# ELoad_Control_Assembly_Gen_2_-_PSU_-_Rev.net
KiCad netlist of a schematic drawn in Altium Designer
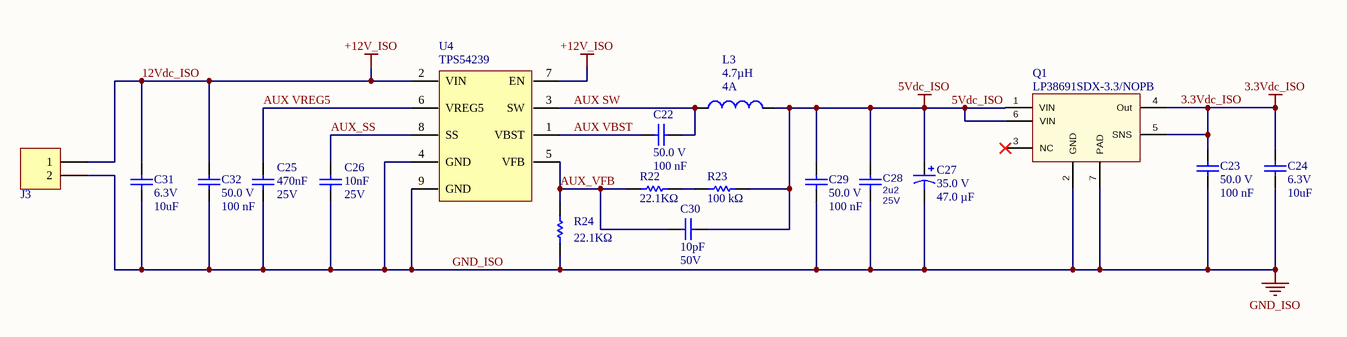
[diagram p0: ELoad Control Assembly Gen 2 - PSU - Rev 2.SchDoc]

(export (version "E")
  (design (tool "Eeschema 10.0.6"))
  (components
    (comp (ref "C22")
      (value "Cap")
      (footprint "Cap,0805")
      (description "Capacitor; Ceramic; Cap 0.1 uF; Tol 5%; Vol-Rtg 50 VDC; SMT; 0805; X7R; Tape & Reel")
      (fields
        (field (name "MANUFACTURER PART NUMBER") "08055C104JAT2A")
        (field (name "VOLTAGE RATING (DC)") "50.0 V")
        (field (name "CAPACITANCE") "100 nF")
      )
      (libsource (lib "Master SEPT2019") (part "Cap,0805,100nf,50V,5%,08055C104JAT2A"))
    )
    (comp (ref "C23")
      (value "Cap")
      (footprint "Cap,0805")
      (description "Capacitor; Ceramic; Cap 0.1 uF; Tol 5%; Vol-Rtg 50 VDC; SMT; 0805; X7R; Tape & Reel")
      (fields
        (field (name "MANUFACTURER PART NUMBER") "08055C104JAT2A")
        (field (name "VOLTAGE RATING (DC)") "50.0 V")
        (field (name "CAPACITANCE") "100 nF")
      )
      (libsource (lib "Master SEPT2019") (part "Cap,0805,100nf,50V,5%,08055C104JAT2A"))
    )
    (comp (ref "C24")
      (value "Cap")
      (footprint "Cap,0805")
      (description "CL21 Series 10 uF 6.3V ±10 % Tolerance X5R SMT Multilayer Ceramic Capacitor")
      (fields
        (field (name "TOLERANCE") "±10%")
        (field (name "VOLTAGE - RATED") "6.3V")
        (field (name "CAPACITANCE") "10uF")
      )
      (libsource (lib "Master SEPT2019") (part "Cap,0805,10uf,6.3V,10%,CL21A106KQFNNNG"))
    )
    (comp (ref "C25")
      (value "Cap")
      (footprint "Cap,0805")
      (description "0.47µF ±10% 25V Ceramic Capacitor X7R 0805 (2012 Metric)")
      (fields
        (field (name "MANUFACTURER") "TDK Corporation")
        (field (name "VOLTAGE RATING (DC)") "25V")
        (field (name "CAPACITANCE") "470nF")
      )
      (libsource (lib "Master SEPT2019") (part "Cap,0805,470nf,25V,10%,CGA4J2X7R1E474K125AA"))
    )
    (comp (ref "C26")
      (value "Cap")
      (footprint "Cap,0805")
      (description "CAP CER 10000PF 25V X7R 0805")
      (fields
        (field (name "MANUFACTURER") "Samsung Electro-Mechanics")
        (field (name "VOLTAGE RATING (DC)") "25V")
        (field (name "CAPACITANCE") "10nF")
      )
      (libsource (lib "Master SEPT2019") (part "Cap,0805,10nF,±10%,25Vdc"))
    )
    (comp (ref "C27")
      (value "Nichicon UCW1V470MCL1GS")
      (footprint "Cap, SMD, polerized, 5mm spacing")
      (description "47uF 35 V dc Aluminium Electrolytic Capacitor, CW Series 7000h 6.3(Dia.)x8.7mm")
      (fields
        (field (name "MANUFACTURER PART NUMBER") "UCW1V470MCL1GS")
        (field (name "VOLTAGE RATING (DC)") "35.0 V")
        (field (name "CAPACITANCE") "47.0 µF")
      )
      (libsource (lib "Master SEPT2019") (part "Cap, Polar,SMD, 47uF,35V,UCW1V470MCL1GS"))
    )
    (comp (ref "C28")
      (value "2u2")
      (footprint "res, 0805, HD")
      (description "Cap,SMD,MLCC,2.2uF 25V X7R 10%,0805")
      (fields (field (name "MANUFACTURER") "Murata") (field (name "VOLTAGE") "25V"))
      (libsource (lib "Master SEPT_2019") (part "Cap,0805,2.2uF,10%,25V"))
    )
    (comp (ref "C29")
      (value "Cap")
      (footprint "Cap,0805")
      (description "Capacitor; Ceramic; Cap 0.1 uF; Tol 5%; Vol-Rtg 50 VDC; SMT; 0805; X7R; Tape & Reel")
      (fields
        (field (name "MANUFACTURER PART NUMBER") "08055C104JAT2A")
        (field (name "VOLTAGE RATING (DC)") "50.0 V")
        (field (name "CAPACITANCE") "100 nF")
      )
      (libsource (lib "Master SEPT_2019") (part "Cap,0805,100nf,50V,5%,08055C104JAT2A"))
    )
    (comp (ref "C30")
      (value "CL21C100JBANNNC")
      (footprint "CAP, 0805, HD")
      (description "CAP CER 10PF 50V C0G/NP0 0805")
      (fields
        (field (name "MANUFACTURER") "Samsung Electro-Mechanics")
        (field (name "TOLERANCE") "±5%")
        (field (name "CAPACITANCE") "10pF")
        (field (name "VOLTAGE - RATED") "50V")
      )
      (libsource (lib "Master SEPT_2019") (part "Cap,0805,10pf,±5%,C0G, NP0,CL21C100JBANNNC"))
    )
    (comp (ref "C31")
      (value "Cap")
      (footprint "Cap,0805")
      (description "CL21 Series 10 uF 6.3V ±10 % Tolerance X5R SMT Multilayer Ceramic Capacitor")
      (fields
        (field (name "TOLERANCE") "±10%")
        (field (name "VOLTAGE - RATED") "6.3V")
        (field (name "CAPACITANCE") "10uF")
      )
      (libsource (lib "Master SEPT2019") (part "Cap,0805,10uf,6.3V,10%,CL21A106KQFNNNG"))
    )
    (comp (ref "C32")
      (value "Cap")
      (footprint "Cap,0805")
      (description "Capacitor; Ceramic; Cap 0.1 uF; Tol 5%; Vol-Rtg 50 VDC; SMT; 0805; X7R; Tape & Reel")
      (fields
        (field (name "MANUFACTURER PART NUMBER") "08055C104JAT2A")
        (field (name "VOLTAGE RATING (DC)") "50.0 V")
        (field (name "CAPACITANCE") "100 nF")
      )
      (libsource (lib "Master SEPT2019") (part "Cap,0805,100nf,50V,5%,08055C104JAT2A"))
    )
    (comp (ref "J3")
      (value "conn, through hole, molex, 2 pin, 0.1\",640456-2")
      (footprint "Conn, Molex, 2pin,0.1\" spacing")
      (description "Header, Friction Lock; MTA-100; 2; 250 VAC; Polyester; Tin; Copper Alloy; Tin")
      (libsource (lib "Master JULY2019") (part "conn, through hole, molex, 2 pin, 0.1{dblquote},640456-2"))
    )
    (comp (ref "L3")
      (value "1255AY-4R7M=P3")
      (footprint "Ind,Non-Stand,Murata,1255AY")
      (description "FIXED IND 4.7UH 4.5A 27.6 MOHM")
      (fields
        (field (name "MANUFACTURER") "Murata Electronics North America")
        (field (name "TOLERANCE") "±20%")
        (field (name "INDUCTANCE") "4.7µH")
        (field (name "CURRENT RATING (AMPS)") "4A")
      )
      (libsource (lib "Master SEPT_2019") (part "IND,NON-Stand,SMD,4.7uH,4.5A,27.6mOhm,1255AY-4R7M=P3"))
    )
    (comp (ref "Q1")
      (value "LP38691SDX-3.3/NOPB")
      (footprint "6-WSON (3x3)")
      (description "IC REG LIN POS ADJ 500MA 6WSON")
      (fields
        (field (name "MFG P/N") "LP38691SDX-3.3/NOPB")
        (field (name "MANUFACTURER") "Texas Instruments")
        (field (name "BASE PART NUMBER") "LP38691")
      )
      (libsource (lib "Master SEPT2019") (part "Reg,Linear,Fixed,500mA,10Vin_Max,3.3Vdc,LP38691SD-ADJ/NOPB"))
    )
    (comp (ref "R22")
      (value "RC0805FR-0722K1L")
      (footprint "res, 0805, HD")
      (description "22.1 kOhms ±1% 0.125W, 1/8W Chip Resistor 0805 (2012 Metric) Moisture Resistant Thick Film")
      (fields (field (name "RESISTANCE") "22.1KΩ"))
      (libsource (lib "Master SEPT_2019") (part "Res,0805,22.1K,1%,100ppm,RC0805FR-0722K1L"))
    )
    (comp (ref "R23")
      (value "Res,0805,100kΩ,1%,100ppm,CRCW0805100KFKEA")
      (footprint "res, 0805, HD")
      (description "100 kOhms ±1% 0.125W, 1/8W Chip Resistor 0805 (2012 Metric) Thick Film")
      (fields
        (field (name "MANUFACTURER PART NUMBER") "CRCW0805100KFKEA")
        (field (name "MANUFACTURER") "Vishay")
        (field (name "RESISTANCE") "100 kΩ")
      )
      (libsource (lib "Master SEPT2019") (part "Res,0805,100kΩ,1%,100ppm,CRCW0805100KFKEA"))
    )
    (comp (ref "R24")
      (value "RC0805FR-0722K1L")
      (footprint "res, 0805, HD")
      (description "22.1 kOhms ±1% 0.125W, 1/8W Chip Resistor 0805 (2012 Metric) Moisture Resistant Thick Film")
      (fields (field (name "RESISTANCE") "22.1KΩ"))
      (libsource (lib "Master SEPT_2019") (part "Res,0805,22.1K,1%,100ppm,RC0805FR-0722K1L"))
    )
    (comp (ref "U4")
      (value "TPS54239")
      (footprint "SOIC-8 PowerPad(pin4)")
      (libsource (lib "Master SEPT_2019") (part "Reg, Switching, Buck,23-4.5Vdcin,2A,TPS54239EDDAR"))
    )
  )
  (nets
    (net (code "1") (name "+12V_ISO") (class "Default")
      (node (ref "C31") (pin "2") (pinfunction "2_2") (pintype "passive"))
      (node (ref "C32") (pin "2") (pinfunction "2_2") (pintype "passive"))
      (node (ref "J3") (pin "1") (pinfunction "1_1") (pintype "passive"))
      (node (ref "U4") (pin "2") (pinfunction "VIN_2") (pintype "passive"))
      (node (ref "U4") (pin "7") (pinfunction "EN_7") (pintype "passive"))
    )
    (net (code "2") (name "/AUX SW") (class "Default")
      (node (ref "C22") (pin "1") (pinfunction "1_1") (pintype "passive"))
      (node (ref "L3") (pin "1") (pinfunction "1_1") (pintype "passive"))
      (node (ref "U4") (pin "3") (pinfunction "SW_3") (pintype "passive"))
    )
    (net (code "3") (name "/AUX VBST") (class "Default")
      (node (ref "C22") (pin "2") (pinfunction "2_2") (pintype "passive"))
      (node (ref "U4") (pin "1") (pinfunction "VBST_1") (pintype "passive"))
    )
    (net (code "4") (name "/AUX VREG5") (class "Default")
      (node (ref "C25") (pin "2") (pinfunction "2_2") (pintype "passive"))
      (node (ref "U4") (pin "6") (pinfunction "VREG5_6") (pintype "passive"))
    )
    (net (code "5") (name "/AUX_SS") (class "Default")
      (node (ref "C26") (pin "2") (pinfunction "2_2") (pintype "passive"))
      (node (ref "U4") (pin "8") (pinfunction "SS_8") (pintype "passive"))
    )
    (net (code "6") (name "/AUX_VFB") (class "Default")
      (node (ref "C30") (pin "2") (pinfunction "2_2") (pintype "passive"))
      (node (ref "R22") (pin "1") (pinfunction "1_1") (pintype "passive"))
      (node (ref "R24") (pin "2") (pinfunction "2_2") (pintype "passive"))
      (node (ref "U4") (pin "5") (pinfunction "VFB_5") (pintype "passive"))
    )
    (net (code "7") (name "3.3Vdc_ISO") (class "Default")
      (node (ref "C23") (pin "2") (pinfunction "2_2") (pintype "passive"))
      (node (ref "C24") (pin "2") (pinfunction "2_2") (pintype "passive"))
      (node (ref "Q1") (pin "4") (pinfunction "Out_4") (pintype "power_in"))
      (node (ref "Q1") (pin "5") (pinfunction "SNS_5") (pintype "passive"))
    )
    (net (code "8") (name "5Vdc_ISO") (class "Default")
      (node (ref "C27") (pin "1") (pinfunction "1_1") (pintype "passive"))
      (node (ref "C28") (pin "2") (pintype "passive"))
      (node (ref "C29") (pin "2") (pinfunction "2_2") (pintype "passive"))
      (node (ref "C30") (pin "1") (pinfunction "1_1") (pintype "passive"))
      (node (ref "L3") (pin "2") (pinfunction "2_2") (pintype "passive"))
      (node (ref "Q1") (pin "1") (pinfunction "VIN_1") (pintype "power_in"))
      (node (ref "Q1") (pin "6") (pinfunction "VIN_6") (pintype "power_in"))
      (node (ref "R23") (pin "1") (pinfunction "1_1") (pintype "passive"))
    )
    (net (code "9") (name "GND_ISO") (class "Default")
      (node (ref "C23") (pin "1") (pinfunction "1_1") (pintype "passive"))
      (node (ref "C24") (pin "1") (pinfunction "1_1") (pintype "passive"))
      (node (ref "C25") (pin "1") (pinfunction "1_1") (pintype "passive"))
      (node (ref "C26") (pin "1") (pinfunction "1_1") (pintype "passive"))
      (node (ref "C27") (pin "2") (pinfunction "2_2") (pintype "passive"))
      (node (ref "C28") (pin "1") (pintype "passive"))
      (node (ref "C29") (pin "1") (pinfunction "1_1") (pintype "passive"))
      (node (ref "C31") (pin "1") (pinfunction "1_1") (pintype "passive"))
      (node (ref "C32") (pin "1") (pinfunction "1_1") (pintype "passive"))
      (node (ref "J3") (pin "2") (pinfunction "2_2") (pintype "passive"))
      (node (ref "Q1") (pin "2") (pinfunction "GND_2") (pintype "power_in"))
      (node (ref "Q1") (pin "7") (pinfunction "PAD_7") (pintype "power_in"))
      (node (ref "R24") (pin "1") (pinfunction "1_1") (pintype "passive"))
      (node (ref "U4") (pin "4") (pinfunction "GND_4") (pintype "passive"))
      (node (ref "U4") (pin "9") (pinfunction "GND_9") (pintype "passive"))
    )
    (net (code "10") (name "Net-(R22-Pad2)") (class "Default")
      (node (ref "R22") (pin "2") (pinfunction "2_2") (pintype "passive"))
      (node (ref "R23") (pin "2") (pinfunction "2_2") (pintype "passive"))
    )
    (net (code "11") (name "unconnected-(Q1-NC-Pad3)") (class "Default")
      (node (ref "Q1") (pin "3") (pinfunction "NC_3") (pintype "passive+no_connect"))
    )
  )
)
